# BNC.net
KiCad netlist of a schematic drawn in Altium Designer
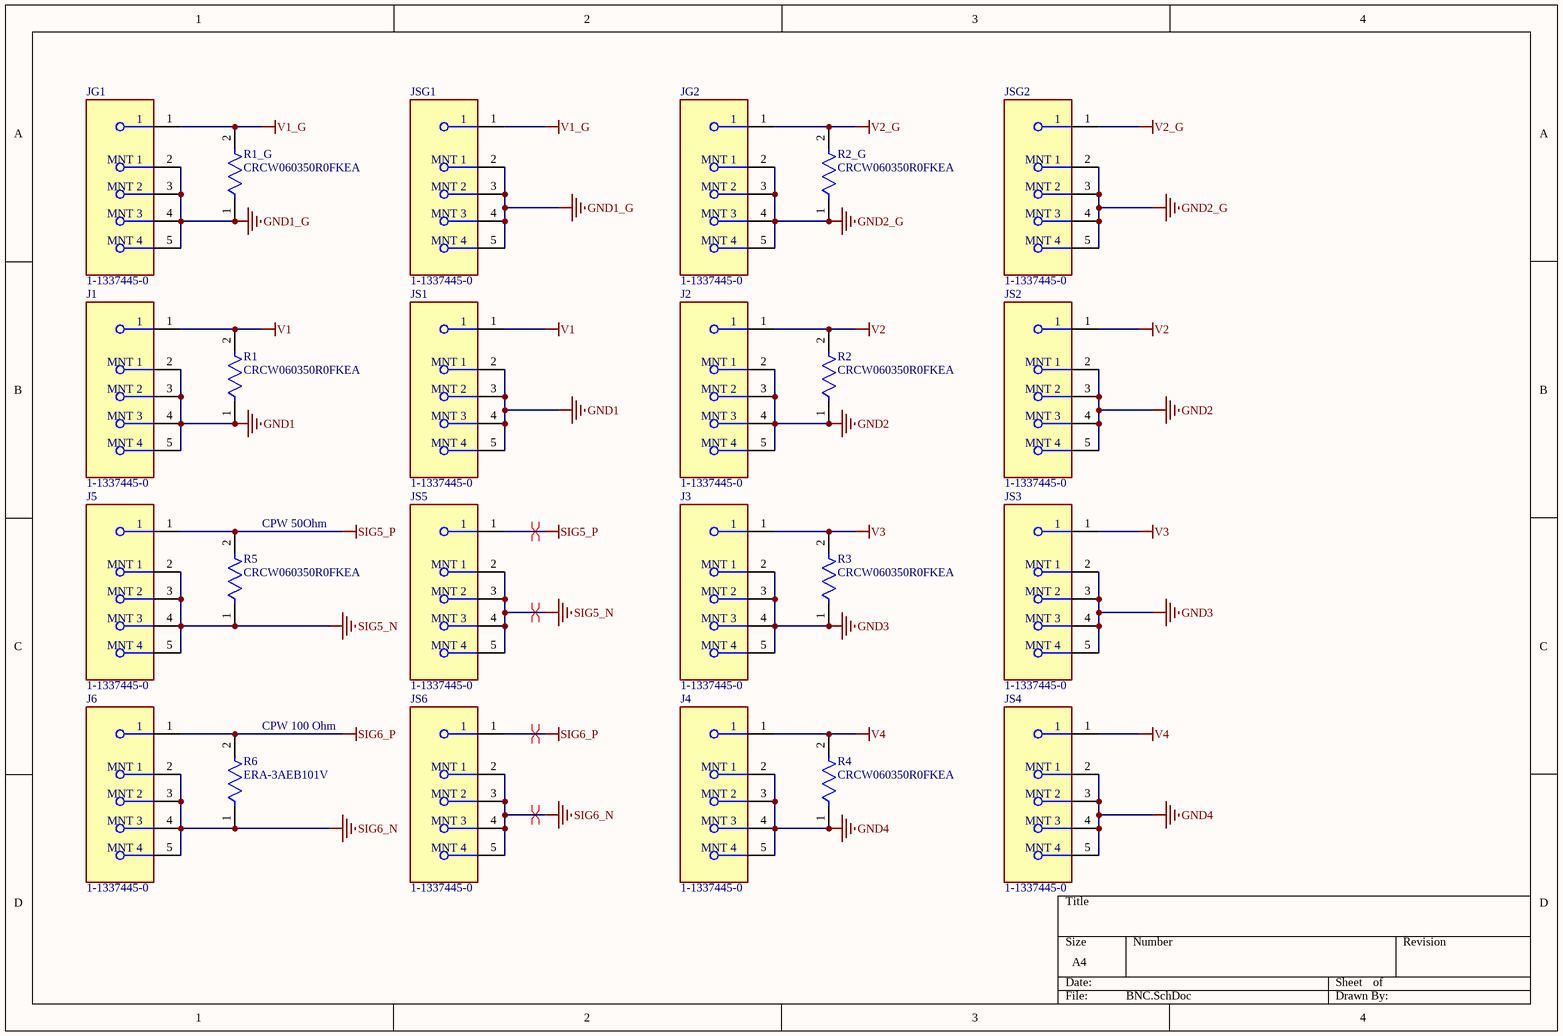
[diagram p0: BNC.SchDoc]

(export (version "E")
  (design (tool "Eeschema 10.0.6"))
  (components
    (comp (ref "J1")
      (value "1-1337445-0")
      (footprint "FP-1-1337445-0-MFG")
      (description "CONN BNC JACK STR 50 OHM PCB")
      (libsource (lib "Altium Content Vault") (part "c65b8a639cdaef1819ea20b5466f8fa"))
    )
    (comp (ref "J2")
      (value "1-1337445-0")
      (footprint "FP-1-1337445-0-MFG")
      (description "CONN BNC JACK STR 50 OHM PCB")
      (libsource (lib "Altium Content Vault") (part "c65b8a639cdaef1819ea20b5466f8fa"))
    )
    (comp (ref "J3")
      (value "1-1337445-0")
      (footprint "FP-1-1337445-0-MFG")
      (description "CONN BNC JACK STR 50 OHM PCB")
      (libsource (lib "Altium Content Vault") (part "c65b8a639cdaef1819ea20b5466f8fa"))
    )
    (comp (ref "J4")
      (value "1-1337445-0")
      (footprint "FP-1-1337445-0-MFG")
      (description "CONN BNC JACK STR 50 OHM PCB")
      (libsource (lib "Altium Content Vault") (part "c65b8a639cdaef1819ea20b5466f8fa"))
    )
    (comp (ref "J5")
      (value "1-1337445-0")
      (footprint "FP-1-1337445-0-MFG")
      (description "CONN BNC JACK STR 50 OHM PCB")
      (libsource (lib "Altium Content Vault") (part "c65b8a639cdaef1819ea20b5466f8fa"))
    )
    (comp (ref "J6")
      (value "1-1337445-0")
      (footprint "FP-1-1337445-0-MFG")
      (description "CONN BNC JACK STR 50 OHM PCB")
      (libsource (lib "Altium Content Vault") (part "c65b8a639cdaef1819ea20b5466f8fa"))
    )
    (comp (ref "JG1")
      (value "1-1337445-0")
      (footprint "FP-1-1337445-0-MFG")
      (description "CONN BNC JACK STR 50 OHM PCB")
      (libsource (lib "Altium Content Vault") (part "c65b8a639cdaef1819ea20b5466f8fa"))
    )
    (comp (ref "JG2")
      (value "1-1337445-0")
      (footprint "FP-1-1337445-0-MFG")
      (description "CONN BNC JACK STR 50 OHM PCB")
      (libsource (lib "Altium Content Vault") (part "c65b8a639cdaef1819ea20b5466f8fa"))
    )
    (comp (ref "JS1")
      (value "1-1337445-0")
      (footprint "FP-1-1337445-0-MFG")
      (description "CONN BNC JACK STR 50 OHM PCB")
      (libsource (lib "Altium Content Vault") (part "c65b8a639cdaef1819ea20b5466f8fa"))
    )
    (comp (ref "JS2")
      (value "1-1337445-0")
      (footprint "FP-1-1337445-0-MFG")
      (description "CONN BNC JACK STR 50 OHM PCB")
      (libsource (lib "Altium Content Vault") (part "c65b8a639cdaef1819ea20b5466f8fa"))
    )
    (comp (ref "JS3")
      (value "1-1337445-0")
      (footprint "FP-1-1337445-0-MFG")
      (description "CONN BNC JACK STR 50 OHM PCB")
      (libsource (lib "Altium Content Vault") (part "c65b8a639cdaef1819ea20b5466f8fa"))
    )
    (comp (ref "JS4")
      (value "1-1337445-0")
      (footprint "FP-1-1337445-0-MFG")
      (description "CONN BNC JACK STR 50 OHM PCB")
      (libsource (lib "Altium Content Vault") (part "c65b8a639cdaef1819ea20b5466f8fa"))
    )
    (comp (ref "JS5")
      (value "1-1337445-0")
      (footprint "FP-1-1337445-0-MFG")
      (description "CONN BNC JACK STR 50 OHM PCB")
      (libsource (lib "Altium Content Vault") (part "c65b8a639cdaef1819ea20b5466f8fa"))
    )
    (comp (ref "JS6")
      (value "1-1337445-0")
      (footprint "FP-1-1337445-0-MFG")
      (description "CONN BNC JACK STR 50 OHM PCB")
      (libsource (lib "Altium Content Vault") (part "c65b8a639cdaef1819ea20b5466f8fa"))
    )
    (comp (ref "JSG1")
      (value "1-1337445-0")
      (footprint "FP-1-1337445-0-MFG")
      (description "CONN BNC JACK STR 50 OHM PCB")
      (libsource (lib "Altium Content Vault") (part "c65b8a639cdaef1819ea20b5466f8fa"))
    )
    (comp (ref "JSG2")
      (value "1-1337445-0")
      (footprint "FP-1-1337445-0-MFG")
      (description "CONN BNC JACK STR 50 OHM PCB")
      (libsource (lib "Altium Content Vault") (part "c65b8a639cdaef1819ea20b5466f8fa"))
    )
    (comp (ref "R1")
      (value "CRCW060350R0FKEA")
      (footprint "FP-CRCW0603-e3-MFG")
      (description "RES Thick Film, 50Ω, 1%, 0.1W, 100ppm/°C, 0603")
      (fields (field (name "TOLERANCE") "1%"))
      (libsource (lib "Altium Content Vault") (part "1029c3af85768c4190bb7ad29bc67b5"))
    )
    (comp (ref "R1_G")
      (value "CRCW060350R0FKEA")
      (footprint "FP-CRCW0603-e3-MFG")
      (description "RES Thick Film, 50Ω, 1%, 0.1W, 100ppm/°C, 0603")
      (fields (field (name "TOLERANCE") "1%"))
      (libsource (lib "Altium Content Vault") (part "1029c3af85768c4190bb7ad29bc67b5"))
    )
    (comp (ref "R2")
      (value "CRCW060350R0FKEA")
      (footprint "FP-CRCW0603-e3-MFG")
      (description "RES Thick Film, 50Ω, 1%, 0.1W, 100ppm/°C, 0603")
      (fields (field (name "TOLERANCE") "1%"))
      (libsource (lib "Altium Content Vault") (part "1029c3af85768c4190bb7ad29bc67b5"))
    )
    (comp (ref "R2_G")
      (value "CRCW060350R0FKEA")
      (footprint "FP-CRCW0603-e3-MFG")
      (description "RES Thick Film, 50Ω, 1%, 0.1W, 100ppm/°C, 0603")
      (fields (field (name "TOLERANCE") "1%"))
      (libsource (lib "Altium Content Vault") (part "1029c3af85768c4190bb7ad29bc67b5"))
    )
    (comp (ref "R3")
      (value "CRCW060350R0FKEA")
      (footprint "FP-CRCW0603-e3-MFG")
      (description "RES Thick Film, 50Ω, 1%, 0.1W, 100ppm/°C, 0603")
      (fields (field (name "TOLERANCE") "1%"))
      (libsource (lib "Altium Content Vault") (part "1029c3af85768c4190bb7ad29bc67b5"))
    )
    (comp (ref "R4")
      (value "CRCW060350R0FKEA")
      (footprint "FP-CRCW0603-e3-MFG")
      (description "RES Thick Film, 50Ω, 1%, 0.1W, 100ppm/°C, 0603")
      (fields (field (name "TOLERANCE") "1%"))
      (libsource (lib "Altium Content Vault") (part "1029c3af85768c4190bb7ad29bc67b5"))
    )
    (comp (ref "R5")
      (value "CRCW060350R0FKEA")
      (footprint "FP-CRCW0603-e3-MFG")
      (description "RES Thick Film, 50Ω, 1%, 0.1W, 100ppm/°C, 0603")
      (fields (field (name "TOLERANCE") "1%"))
      (libsource (lib "Altium Content Vault") (part "1029c3af85768c4190bb7ad29bc67b5"))
    )
    (comp (ref "R6")
      (value "ERA-3AEB101V")
      (footprint "FP-ERA3A-IPC_B")
      (description "RES SMD 100 OHM 0.1% 1/10W 0603")
      (fields (field (name "TOLERANCE") "0.1%"))
      (libsource (lib "Altium Content Vault") (part "1029c3af85768c4190bb7ad29bc67b5"))
    )
  )
  (nets
    (net (code "1") (name "GND1") (class "Default")
      (node (ref "J1") (pin "2") (pinfunction "MNT_1_2") (pintype "passive"))
      (node (ref "J1") (pin "3") (pinfunction "MNT_2_3") (pintype "passive"))
      (node (ref "J1") (pin "4") (pinfunction "MNT_3_4") (pintype "passive"))
      (node (ref "J1") (pin "5") (pinfunction "MNT_4_5") (pintype "passive"))
      (node (ref "JS1") (pin "2") (pinfunction "MNT_1_2") (pintype "passive"))
      (node (ref "JS1") (pin "3") (pinfunction "MNT_2_3") (pintype "passive"))
      (node (ref "JS1") (pin "4") (pinfunction "MNT_3_4") (pintype "passive"))
      (node (ref "JS1") (pin "5") (pinfunction "MNT_4_5") (pintype "passive"))
      (node (ref "R1") (pin "1") (pinfunction "1_1") (pintype "passive"))
    )
    (net (code "2") (name "GND1_G") (class "Default")
      (node (ref "JG1") (pin "2") (pinfunction "MNT_1_2") (pintype "passive"))
      (node (ref "JG1") (pin "3") (pinfunction "MNT_2_3") (pintype "passive"))
      (node (ref "JG1") (pin "4") (pinfunction "MNT_3_4") (pintype "passive"))
      (node (ref "JG1") (pin "5") (pinfunction "MNT_4_5") (pintype "passive"))
      (node (ref "JSG1") (pin "2") (pinfunction "MNT_1_2") (pintype "passive"))
      (node (ref "JSG1") (pin "3") (pinfunction "MNT_2_3") (pintype "passive"))
      (node (ref "JSG1") (pin "4") (pinfunction "MNT_3_4") (pintype "passive"))
      (node (ref "JSG1") (pin "5") (pinfunction "MNT_4_5") (pintype "passive"))
      (node (ref "R1_G") (pin "1") (pinfunction "1_1") (pintype "passive"))
    )
    (net (code "3") (name "GND2") (class "Default")
      (node (ref "J2") (pin "2") (pinfunction "MNT_1_2") (pintype "passive"))
      (node (ref "J2") (pin "3") (pinfunction "MNT_2_3") (pintype "passive"))
      (node (ref "J2") (pin "4") (pinfunction "MNT_3_4") (pintype "passive"))
      (node (ref "J2") (pin "5") (pinfunction "MNT_4_5") (pintype "passive"))
      (node (ref "JS2") (pin "2") (pinfunction "MNT_1_2") (pintype "passive"))
      (node (ref "JS2") (pin "3") (pinfunction "MNT_2_3") (pintype "passive"))
      (node (ref "JS2") (pin "4") (pinfunction "MNT_3_4") (pintype "passive"))
      (node (ref "JS2") (pin "5") (pinfunction "MNT_4_5") (pintype "passive"))
      (node (ref "R2") (pin "1") (pinfunction "1_1") (pintype "passive"))
    )
    (net (code "4") (name "GND2_G") (class "Default")
      (node (ref "JG2") (pin "2") (pinfunction "MNT_1_2") (pintype "passive"))
      (node (ref "JG2") (pin "3") (pinfunction "MNT_2_3") (pintype "passive"))
      (node (ref "JG2") (pin "4") (pinfunction "MNT_3_4") (pintype "passive"))
      (node (ref "JG2") (pin "5") (pinfunction "MNT_4_5") (pintype "passive"))
      (node (ref "JSG2") (pin "2") (pinfunction "MNT_1_2") (pintype "passive"))
      (node (ref "JSG2") (pin "3") (pinfunction "MNT_2_3") (pintype "passive"))
      (node (ref "JSG2") (pin "4") (pinfunction "MNT_3_4") (pintype "passive"))
      (node (ref "JSG2") (pin "5") (pinfunction "MNT_4_5") (pintype "passive"))
      (node (ref "R2_G") (pin "1") (pinfunction "1_1") (pintype "passive"))
    )
    (net (code "5") (name "GND3") (class "Default")
      (node (ref "J3") (pin "2") (pinfunction "MNT_1_2") (pintype "passive"))
      (node (ref "J3") (pin "3") (pinfunction "MNT_2_3") (pintype "passive"))
      (node (ref "J3") (pin "4") (pinfunction "MNT_3_4") (pintype "passive"))
      (node (ref "J3") (pin "5") (pinfunction "MNT_4_5") (pintype "passive"))
      (node (ref "JS3") (pin "2") (pinfunction "MNT_1_2") (pintype "passive"))
      (node (ref "JS3") (pin "3") (pinfunction "MNT_2_3") (pintype "passive"))
      (node (ref "JS3") (pin "4") (pinfunction "MNT_3_4") (pintype "passive"))
      (node (ref "JS3") (pin "5") (pinfunction "MNT_4_5") (pintype "passive"))
      (node (ref "R3") (pin "1") (pinfunction "1_1") (pintype "passive"))
    )
    (net (code "6") (name "GND4") (class "Default")
      (node (ref "J4") (pin "2") (pinfunction "MNT_1_2") (pintype "passive"))
      (node (ref "J4") (pin "3") (pinfunction "MNT_2_3") (pintype "passive"))
      (node (ref "J4") (pin "4") (pinfunction "MNT_3_4") (pintype "passive"))
      (node (ref "J4") (pin "5") (pinfunction "MNT_4_5") (pintype "passive"))
      (node (ref "JS4") (pin "2") (pinfunction "MNT_1_2") (pintype "passive"))
      (node (ref "JS4") (pin "3") (pinfunction "MNT_2_3") (pintype "passive"))
      (node (ref "JS4") (pin "4") (pinfunction "MNT_3_4") (pintype "passive"))
      (node (ref "JS4") (pin "5") (pinfunction "MNT_4_5") (pintype "passive"))
      (node (ref "R4") (pin "1") (pinfunction "1_1") (pintype "passive"))
    )
    (net (code "7") (name "SIG5_N") (class "Default")
      (node (ref "J5") (pin "2") (pinfunction "MNT_1_2") (pintype "passive"))
      (node (ref "J5") (pin "3") (pinfunction "MNT_2_3") (pintype "passive"))
      (node (ref "J5") (pin "4") (pinfunction "MNT_3_4") (pintype "passive"))
      (node (ref "J5") (pin "5") (pinfunction "MNT_4_5") (pintype "passive"))
      (node (ref "JS5") (pin "2") (pinfunction "MNT_1_2") (pintype "passive"))
      (node (ref "JS5") (pin "3") (pinfunction "MNT_2_3") (pintype "passive"))
      (node (ref "JS5") (pin "4") (pinfunction "MNT_3_4") (pintype "passive"))
      (node (ref "JS5") (pin "5") (pinfunction "MNT_4_5") (pintype "passive"))
      (node (ref "R5") (pin "1") (pinfunction "1_1") (pintype "passive"))
    )
    (net (code "8") (name "SIG5_P") (class "Default")
      (node (ref "J5") (pin "1") (pinfunction "1_1") (pintype "passive"))
      (node (ref "JS5") (pin "1") (pinfunction "1_1") (pintype "passive"))
      (node (ref "R5") (pin "2") (pinfunction "2_2") (pintype "passive"))
    )
    (net (code "9") (name "SIG6_N") (class "Default")
      (node (ref "J6") (pin "2") (pinfunction "MNT_1_2") (pintype "passive"))
      (node (ref "J6") (pin "3") (pinfunction "MNT_2_3") (pintype "passive"))
      (node (ref "J6") (pin "4") (pinfunction "MNT_3_4") (pintype "passive"))
      (node (ref "J6") (pin "5") (pinfunction "MNT_4_5") (pintype "passive"))
      (node (ref "JS6") (pin "2") (pinfunction "MNT_1_2") (pintype "passive"))
      (node (ref "JS6") (pin "3") (pinfunction "MNT_2_3") (pintype "passive"))
      (node (ref "JS6") (pin "4") (pinfunction "MNT_3_4") (pintype "passive"))
      (node (ref "JS6") (pin "5") (pinfunction "MNT_4_5") (pintype "passive"))
      (node (ref "R6") (pin "1") (pinfunction "1_1") (pintype "passive"))
    )
    (net (code "10") (name "SIG6_P") (class "Default")
      (node (ref "J6") (pin "1") (pinfunction "1_1") (pintype "passive"))
      (node (ref "JS6") (pin "1") (pinfunction "1_1") (pintype "passive"))
      (node (ref "R6") (pin "2") (pinfunction "2_2") (pintype "passive"))
    )
    (net (code "11") (name "V1") (class "Default")
      (node (ref "J1") (pin "1") (pinfunction "1_1") (pintype "passive"))
      (node (ref "JS1") (pin "1") (pinfunction "1_1") (pintype "passive"))
      (node (ref "R1") (pin "2") (pinfunction "2_2") (pintype "passive"))
    )
    (net (code "12") (name "V1_G") (class "Default")
      (node (ref "JG1") (pin "1") (pinfunction "1_1") (pintype "passive"))
      (node (ref "JSG1") (pin "1") (pinfunction "1_1") (pintype "passive"))
      (node (ref "R1_G") (pin "2") (pinfunction "2_2") (pintype "passive"))
    )
    (net (code "13") (name "V2") (class "Default")
      (node (ref "J2") (pin "1") (pinfunction "1_1") (pintype "passive"))
      (node (ref "JS2") (pin "1") (pinfunction "1_1") (pintype "passive"))
      (node (ref "R2") (pin "2") (pinfunction "2_2") (pintype "passive"))
    )
    (net (code "14") (name "V2_G") (class "Default")
      (node (ref "JG2") (pin "1") (pinfunction "1_1") (pintype "passive"))
      (node (ref "JSG2") (pin "1") (pinfunction "1_1") (pintype "passive"))
      (node (ref "R2_G") (pin "2") (pinfunction "2_2") (pintype "passive"))
    )
    (net (code "15") (name "V3") (class "Default")
      (node (ref "J3") (pin "1") (pinfunction "1_1") (pintype "passive"))
      (node (ref "JS3") (pin "1") (pinfunction "1_1") (pintype "passive"))
      (node (ref "R3") (pin "2") (pinfunction "2_2") (pintype "passive"))
    )
    (net (code "16") (name "V4") (class "Default")
      (node (ref "J4") (pin "1") (pinfunction "1_1") (pintype "passive"))
      (node (ref "JS4") (pin "1") (pinfunction "1_1") (pintype "passive"))
      (node (ref "R4") (pin "2") (pinfunction "2_2") (pintype "passive"))
    )
  )
)
